# 6_Nand_Flash_NOR_Flash.net
KiCad netlist of a schematic drawn in Altium Designer
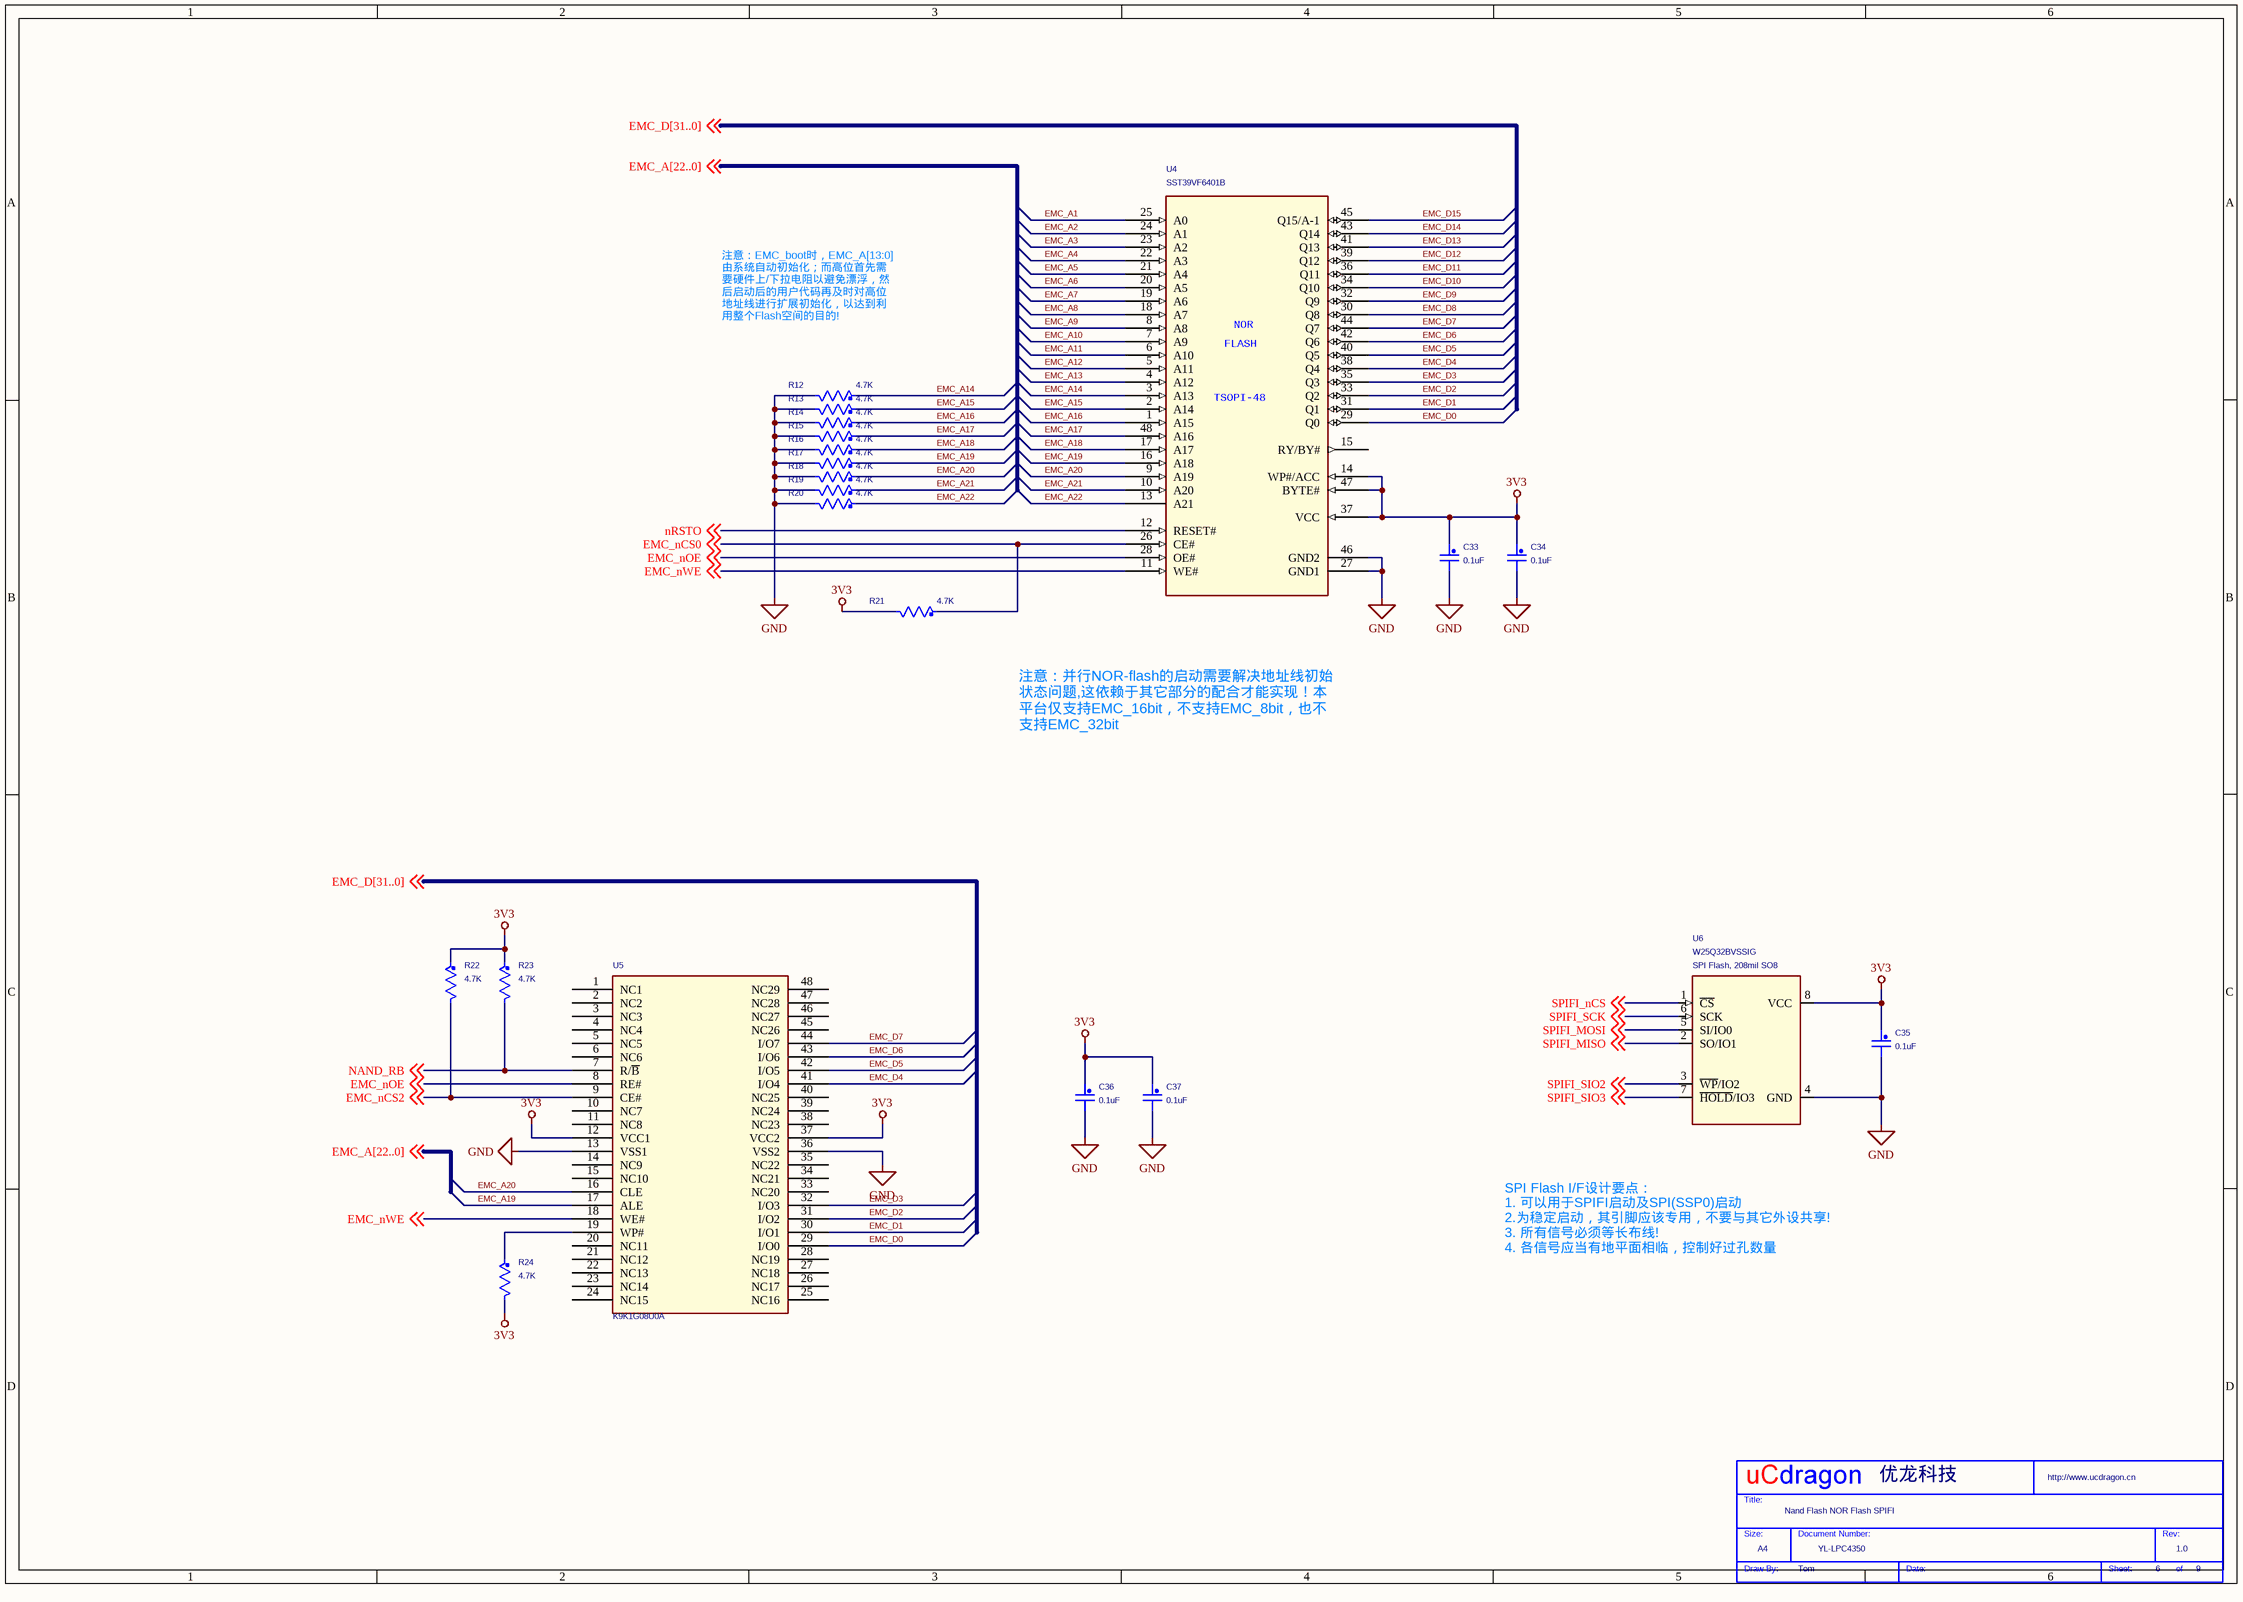
[diagram p0: 6) Nand Flash,NOR Flash.SchDoc]

(export (version "E")
  (design (tool "Eeschema 10.0.6"))
  (components
    (comp (ref "C33")
      (value "0.1uF")
      (footprint "CAP0805")
      (fields (field (name "VOLTAGE") "16V"))
      (libsource (lib "*") (part "C_Generic"))
    )
    (comp (ref "C34")
      (value "0.1uF")
      (footprint "CAP0805")
      (fields (field (name "VOLTAGE") "16V"))
      (libsource (lib "*") (part "C_Generic"))
    )
    (comp (ref "C35")
      (value "0.1uF")
      (footprint "CAP0805")
      (fields (field (name "VOLTAGE") "16V"))
      (libsource (lib "*") (part "C_Generic"))
    )
    (comp (ref "C36")
      (value "0.1uF")
      (footprint "CAP0805")
      (fields (field (name "VOLTAGE") "16V"))
      (libsource (lib "*") (part "C_Generic"))
    )
    (comp (ref "C37")
      (value "0.1uF")
      (footprint "CAP0805")
      (fields (field (name "VOLTAGE") "16V"))
      (libsource (lib "*") (part "C_Generic"))
    )
    (comp (ref "R12") (value "4.7K") (libsource (lib "*") (part "R_Generic_Dup1")))
    (comp (ref "R13") (value "4.7K") (libsource (lib "*") (part "R_Generic_Dup1")))
    (comp (ref "R14") (value "4.7K") (libsource (lib "*") (part "R_Generic_Dup1")))
    (comp (ref "R15") (value "4.7K") (libsource (lib "*") (part "R_Generic_Dup1")))
    (comp (ref "R16") (value "4.7K") (libsource (lib "*") (part "R_Generic_Dup1")))
    (comp (ref "R17") (value "4.7K") (libsource (lib "*") (part "R_Generic_Dup1")))
    (comp (ref "R18") (value "4.7K") (libsource (lib "*") (part "R_Generic_Dup1")))
    (comp (ref "R19") (value "4.7K") (libsource (lib "*") (part "R_Generic_Dup1")))
    (comp (ref "R20") (value "4.7K") (libsource (lib "*") (part "R_Generic_Dup1")))
    (comp (ref "R21") (value "4.7K") (libsource (lib "*") (part "R_Generic_Dup1")))
    (comp (ref "R22") (value "4.7K") (libsource (lib "*") (part "R_Generic_Dup1")))
    (comp (ref "R23") (value "4.7K") (libsource (lib "*") (part "R_Generic_Dup1")))
    (comp (ref "R24") (value "4.7K") (libsource (lib "*") (part "R_Generic_Dup1")))
    (comp (ref "U4")
      (value "SST39VF6401B")
      (footprint "TSOPI-48")
      (libsource (lib "*") (part "MX29LV640EBTI-70G"))
    )
    (comp (ref "U5") (value "K9K1G08U0A") (footprint "TSOP1") (libsource (lib "*") (part "K9K1G08U0A")))
    (comp (ref "U6")
      (value "W25Q32BVSSIG")
      (fields (field (name "NOTE") "SPI Flash, 208mil SO8"))
      (libsource (lib "*") (part "SPI FLASH 4IO WSO8"))
    )
  )
  (nets
    (net (code "1") (name "3V3") (class "Default")
      (node (ref "C33") (pin "1") (pinfunction "1_1") (pintype "passive"))
      (node (ref "C34") (pin "1") (pinfunction "1_1") (pintype "passive"))
      (node (ref "C35") (pin "1") (pinfunction "1_1") (pintype "passive"))
      (node (ref "C36") (pin "1") (pinfunction "1_1") (pintype "passive"))
      (node (ref "C37") (pin "1") (pinfunction "1_1") (pintype "passive"))
      (node (ref "R21") (pin "2") (pinfunction "2_2") (pintype "passive"))
      (node (ref "R22") (pin "1") (pinfunction "1_1") (pintype "passive"))
      (node (ref "R23") (pin "1") (pinfunction "1_1") (pintype "passive"))
      (node (ref "R24") (pin "2") (pinfunction "2_2") (pintype "passive"))
      (node (ref "U4") (pin "14") (pinfunction "WP#/ACC_14") (pintype "input"))
      (node (ref "U4") (pin "37") (pinfunction "VCC_37") (pintype "input"))
      (node (ref "U4") (pin "47") (pinfunction "BYTE#_47") (pintype "input"))
      (node (ref "U5") (pin "12") (pinfunction "VCC1_12") (pintype "passive"))
      (node (ref "U5") (pin "37") (pinfunction "VCC2_37") (pintype "passive"))
      (node (ref "U6") (pin "8") (pinfunction "VCC_8") (pintype "passive"))
    )
    (net (code "2") (name "EMC_A1") (class "Default")
      (node (ref "U4") (pin "25") (pinfunction "A0_25") (pintype "input"))
    )
    (net (code "3") (name "EMC_A2") (class "Default")
      (node (ref "U4") (pin "24") (pinfunction "A1_24") (pintype "input"))
    )
    (net (code "4") (name "EMC_A3") (class "Default")
      (node (ref "U4") (pin "23") (pinfunction "A2_23") (pintype "input"))
    )
    (net (code "5") (name "EMC_A4") (class "Default")
      (node (ref "U4") (pin "22") (pinfunction "A3_22") (pintype "input"))
    )
    (net (code "6") (name "EMC_A5") (class "Default")
      (node (ref "U4") (pin "21") (pinfunction "A4_21") (pintype "input"))
    )
    (net (code "7") (name "EMC_A6") (class "Default")
      (node (ref "U4") (pin "20") (pinfunction "A5_20") (pintype "input"))
    )
    (net (code "8") (name "EMC_A7") (class "Default")
      (node (ref "U4") (pin "19") (pinfunction "A6_19") (pintype "input"))
    )
    (net (code "9") (name "EMC_A8") (class "Default")
      (node (ref "U4") (pin "18") (pinfunction "A7_18") (pintype "input"))
    )
    (net (code "10") (name "EMC_A9") (class "Default")
      (node (ref "U4") (pin "8") (pinfunction "A8_8") (pintype "input"))
    )
    (net (code "11") (name "EMC_A10") (class "Default")
      (node (ref "U4") (pin "7") (pinfunction "A9_7") (pintype "input"))
    )
    (net (code "12") (name "EMC_A11") (class "Default")
      (node (ref "U4") (pin "6") (pinfunction "A10_6") (pintype "input"))
    )
    (net (code "13") (name "EMC_A12") (class "Default")
      (node (ref "U4") (pin "5") (pinfunction "A11_5") (pintype "input"))
    )
    (net (code "14") (name "EMC_A13") (class "Default")
      (node (ref "U4") (pin "4") (pinfunction "A12_4") (pintype "input"))
    )
    (net (code "15") (name "EMC_A14") (class "Default")
      (node (ref "R12") (pin "1") (pinfunction "1_1") (pintype "passive"))
      (node (ref "U4") (pin "3") (pinfunction "A13_3") (pintype "input"))
    )
    (net (code "16") (name "EMC_A15") (class "Default")
      (node (ref "R13") (pin "1") (pinfunction "1_1") (pintype "passive"))
      (node (ref "U4") (pin "2") (pinfunction "A14_2") (pintype "input"))
    )
    (net (code "17") (name "EMC_A16") (class "Default")
      (node (ref "R14") (pin "1") (pinfunction "1_1") (pintype "passive"))
      (node (ref "U4") (pin "1") (pinfunction "A15_1") (pintype "input"))
    )
    (net (code "18") (name "EMC_A17") (class "Default")
      (node (ref "R15") (pin "1") (pinfunction "1_1") (pintype "passive"))
      (node (ref "U4") (pin "48") (pinfunction "A16_48") (pintype "input"))
    )
    (net (code "19") (name "EMC_A18") (class "Default")
      (node (ref "R16") (pin "1") (pinfunction "1_1") (pintype "passive"))
      (node (ref "U4") (pin "17") (pinfunction "A17_17") (pintype "input"))
    )
    (net (code "20") (name "EMC_A19") (class "Default")
      (node (ref "R17") (pin "1") (pinfunction "1_1") (pintype "passive"))
      (node (ref "U4") (pin "16") (pinfunction "A18_16") (pintype "input"))
      (node (ref "U5") (pin "17") (pinfunction "ALE_17") (pintype "passive"))
    )
    (net (code "21") (name "EMC_A20") (class "Default")
      (node (ref "R18") (pin "1") (pinfunction "1_1") (pintype "passive"))
      (node (ref "U4") (pin "9") (pinfunction "A19_9") (pintype "input"))
      (node (ref "U5") (pin "16") (pinfunction "CLE_16") (pintype "passive"))
    )
    (net (code "22") (name "EMC_A21") (class "Default")
      (node (ref "R19") (pin "1") (pinfunction "1_1") (pintype "passive"))
      (node (ref "U4") (pin "10") (pinfunction "A20_10") (pintype "input"))
    )
    (net (code "23") (name "EMC_A22") (class "Default")
      (node (ref "R20") (pin "1") (pinfunction "1_1") (pintype "passive"))
      (node (ref "U4") (pin "13") (pinfunction "A21_13") (pintype "passive"))
    )
    (net (code "25") (name "EMC_D0") (class "Default")
      (node (ref "U4") (pin "29") (pinfunction "Q0_29") (pintype "bidirectional"))
      (node (ref "U5") (pin "29") (pinfunction "I/O0_29") (pintype "passive"))
    )
    (net (code "26") (name "EMC_D1") (class "Default")
      (node (ref "U4") (pin "31") (pinfunction "Q1_31") (pintype "bidirectional"))
      (node (ref "U5") (pin "30") (pinfunction "I/O1_30") (pintype "passive"))
    )
    (net (code "27") (name "EMC_D2") (class "Default")
      (node (ref "U4") (pin "33") (pinfunction "Q2_33") (pintype "bidirectional"))
      (node (ref "U5") (pin "31") (pinfunction "I/O2_31") (pintype "passive"))
    )
    (net (code "28") (name "EMC_D3") (class "Default")
      (node (ref "U4") (pin "35") (pinfunction "Q3_35") (pintype "bidirectional"))
      (node (ref "U5") (pin "32") (pinfunction "I/O3_32") (pintype "passive"))
    )
    (net (code "29") (name "EMC_D4") (class "Default")
      (node (ref "U4") (pin "38") (pinfunction "Q4_38") (pintype "bidirectional"))
      (node (ref "U5") (pin "41") (pinfunction "I/O4_41") (pintype "passive"))
    )
    (net (code "30") (name "EMC_D5") (class "Default")
      (node (ref "U4") (pin "40") (pinfunction "Q5_40") (pintype "bidirectional"))
      (node (ref "U5") (pin "42") (pinfunction "I/O5_42") (pintype "passive"))
    )
    (net (code "31") (name "EMC_D6") (class "Default")
      (node (ref "U4") (pin "42") (pinfunction "Q6_42") (pintype "bidirectional"))
      (node (ref "U5") (pin "43") (pinfunction "I/O6_43") (pintype "passive"))
    )
    (net (code "32") (name "EMC_D7") (class "Default")
      (node (ref "U4") (pin "44") (pinfunction "Q7_44") (pintype "bidirectional"))
      (node (ref "U5") (pin "44") (pinfunction "I/O7_44") (pintype "passive"))
    )
    (net (code "33") (name "EMC_D8") (class "Default")
      (node (ref "U4") (pin "30") (pinfunction "Q8_30") (pintype "bidirectional"))
    )
    (net (code "34") (name "EMC_D9") (class "Default")
      (node (ref "U4") (pin "32") (pinfunction "Q9_32") (pintype "bidirectional"))
    )
    (net (code "35") (name "EMC_D10") (class "Default")
      (node (ref "U4") (pin "34") (pinfunction "Q10_34") (pintype "bidirectional"))
    )
    (net (code "36") (name "EMC_D11") (class "Default")
      (node (ref "U4") (pin "36") (pinfunction "Q11_36") (pintype "bidirectional"))
    )
    (net (code "37") (name "EMC_D12") (class "Default")
      (node (ref "U4") (pin "39") (pinfunction "Q12_39") (pintype "bidirectional"))
    )
    (net (code "38") (name "EMC_D13") (class "Default")
      (node (ref "U4") (pin "41") (pinfunction "Q13_41") (pintype "bidirectional"))
    )
    (net (code "39") (name "EMC_D14") (class "Default")
      (node (ref "U4") (pin "43") (pinfunction "Q14_43") (pintype "bidirectional"))
    )
    (net (code "40") (name "EMC_D15") (class "Default")
      (node (ref "U4") (pin "45") (pinfunction "Q15/A-1_45") (pintype "bidirectional"))
    )
    (net (code "42") (name "EMC_nCS0") (class "Default")
      (node (ref "R21") (pin "1") (pinfunction "1_1") (pintype "passive"))
      (node (ref "U4") (pin "26") (pinfunction "CE#_26") (pintype "input"))
    )
    (net (code "43") (name "EMC_nCS2") (class "Default")
      (node (ref "R22") (pin "2") (pinfunction "2_2") (pintype "passive"))
      (node (ref "U5") (pin "9") (pinfunction "CE#_9") (pintype "passive"))
    )
    (net (code "44") (name "EMC_nOE") (class "Default")
      (node (ref "U4") (pin "28") (pinfunction "OE#_28") (pintype "input"))
      (node (ref "U5") (pin "8") (pinfunction "RE#_8") (pintype "passive"))
    )
    (net (code "45") (name "EMC_nWE") (class "Default")
      (node (ref "U4") (pin "11") (pinfunction "WE#_11") (pintype "input"))
      (node (ref "U5") (pin "18") (pinfunction "WE#_18") (pintype "passive"))
    )
    (net (code "46") (name "GND") (class "Default")
      (node (ref "C33") (pin "2") (pinfunction "2_2") (pintype "passive"))
      (node (ref "C34") (pin "2") (pinfunction "2_2") (pintype "passive"))
      (node (ref "C35") (pin "2") (pinfunction "2_2") (pintype "passive"))
      (node (ref "C36") (pin "2") (pinfunction "2_2") (pintype "passive"))
      (node (ref "C37") (pin "2") (pinfunction "2_2") (pintype "passive"))
      (node (ref "R12") (pin "2") (pinfunction "2_2") (pintype "passive"))
      (node (ref "R13") (pin "2") (pinfunction "2_2") (pintype "passive"))
      (node (ref "R14") (pin "2") (pinfunction "2_2") (pintype "passive"))
      (node (ref "R15") (pin "2") (pinfunction "2_2") (pintype "passive"))
      (node (ref "R16") (pin "2") (pinfunction "2_2") (pintype "passive"))
      (node (ref "R17") (pin "2") (pinfunction "2_2") (pintype "passive"))
      (node (ref "R18") (pin "2") (pinfunction "2_2") (pintype "passive"))
      (node (ref "R19") (pin "2") (pinfunction "2_2") (pintype "passive"))
      (node (ref "R20") (pin "2") (pinfunction "2_2") (pintype "passive"))
      (node (ref "U4") (pin "27") (pinfunction "GND1_27") (pintype "passive"))
      (node (ref "U4") (pin "46") (pinfunction "GND2_46") (pintype "passive"))
      (node (ref "U5") (pin "13") (pinfunction "VSS1_13") (pintype "passive"))
      (node (ref "U5") (pin "36") (pinfunction "VSS2_36") (pintype "passive"))
      (node (ref "U6") (pin "4") (pinfunction "GND_4") (pintype "passive"))
    )
    (net (code "47") (name "NAND_RB") (class "Default")
      (node (ref "R23") (pin "2") (pinfunction "2_2") (pintype "passive"))
      (node (ref "U5") (pin "7") (pinfunction "R/~{B}_7") (pintype "passive"))
    )
    (net (code "48") (name "Net-(U5-WP#)") (class "Default")
      (node (ref "R24") (pin "1") (pinfunction "1_1") (pintype "passive"))
      (node (ref "U5") (pin "19") (pinfunction "WP#_19") (pintype "passive"))
    )
    (net (code "49") (name "SPIFI_MISO") (class "Default")
      (node (ref "U6") (pin "2") (pinfunction "SO/IO1_2") (pintype "passive"))
    )
    (net (code "50") (name "SPIFI_MOSI") (class "Default")
      (node (ref "U6") (pin "5") (pinfunction "SI/IO0_5") (pintype "passive"))
    )
    (net (code "51") (name "SPIFI_SCK") (class "Default")
      (node (ref "U6") (pin "6") (pinfunction "SCK_6") (pintype "input"))
    )
    (net (code "52") (name "SPIFI_SIO2") (class "Default")
      (node (ref "U6") (pin "3") (pinfunction "~{WP}/IO2_3") (pintype "passive"))
    )
    (net (code "53") (name "SPIFI_SIO3") (class "Default")
      (node (ref "U6") (pin "7") (pinfunction "~{HOLD}/IO3_7") (pintype "passive"))
    )
    (net (code "54") (name "SPIFI_nCS") (class "Default")
      (node (ref "U6") (pin "1") (pinfunction "~{CS}_1") (pintype "input"))
    )
    (net (code "55") (name "nRSTO") (class "Default")
      (node (ref "U4") (pin "12") (pinfunction "RESET#_12") (pintype "input"))
    )
    (net (code "56") (name "unconnected-(U4-RY{slash}BY#-Pad15)") (class "Default")
      (node (ref "U4") (pin "15") (pinfunction "RY/BY#_15") (pintype "output"))
    )
    (net (code "57") (name "unconnected-(U5-NC1-Pad1)") (class "Default")
      (node (ref "U5") (pin "1") (pinfunction "NC1_1") (pintype "passive"))
    )
    (net (code "58") (name "unconnected-(U5-NC2-Pad2)") (class "Default")
      (node (ref "U5") (pin "2") (pinfunction "NC2_2") (pintype "passive"))
    )
    (net (code "59") (name "unconnected-(U5-NC3-Pad3)") (class "Default")
      (node (ref "U5") (pin "3") (pinfunction "NC3_3") (pintype "passive"))
    )
    (net (code "60") (name "unconnected-(U5-NC4-Pad4)") (class "Default")
      (node (ref "U5") (pin "4") (pinfunction "NC4_4") (pintype "passive"))
    )
    (net (code "61") (name "unconnected-(U5-NC5-Pad5)") (class "Default")
      (node (ref "U5") (pin "5") (pinfunction "NC5_5") (pintype "passive"))
    )
    (net (code "62") (name "unconnected-(U5-NC6-Pad6)") (class "Default")
      (node (ref "U5") (pin "6") (pinfunction "NC6_6") (pintype "passive"))
    )
    (net (code "63") (name "unconnected-(U5-NC7-Pad10)") (class "Default")
      (node (ref "U5") (pin "10") (pinfunction "NC7_10") (pintype "passive"))
    )
    (net (code "64") (name "unconnected-(U5-NC8-Pad11)") (class "Default")
      (node (ref "U5") (pin "11") (pinfunction "NC8_11") (pintype "passive"))
    )
    (net (code "65") (name "unconnected-(U5-NC9-Pad14)") (class "Default")
      (node (ref "U5") (pin "14") (pinfunction "NC9_14") (pintype "passive"))
    )
    (net (code "66") (name "unconnected-(U5-NC10-Pad15)") (class "Default")
      (node (ref "U5") (pin "15") (pinfunction "NC10_15") (pintype "passive"))
    )
    (net (code "67") (name "unconnected-(U5-NC11-Pad20)") (class "Default")
      (node (ref "U5") (pin "20") (pinfunction "NC11_20") (pintype "passive"))
    )
    (net (code "68") (name "unconnected-(U5-NC12-Pad21)") (class "Default")
      (node (ref "U5") (pin "21") (pinfunction "NC12_21") (pintype "passive"))
    )
    (net (code "69") (name "unconnected-(U5-NC13-Pad22)") (class "Default")
      (node (ref "U5") (pin "22") (pinfunction "NC13_22") (pintype "passive"))
    )
    (net (code "70") (name "unconnected-(U5-NC14-Pad23)") (class "Default")
      (node (ref "U5") (pin "23") (pinfunction "NC14_23") (pintype "passive"))
    )
    (net (code "71") (name "unconnected-(U5-NC15-Pad24)") (class "Default")
      (node (ref "U5") (pin "24") (pinfunction "NC15_24") (pintype "passive"))
    )
    (net (code "72") (name "unconnected-(U5-NC16-Pad25)") (class "Default")
      (node (ref "U5") (pin "25") (pinfunction "NC16_25") (pintype "passive"))
    )
    (net (code "73") (name "unconnected-(U5-NC17-Pad26)") (class "Default")
      (node (ref "U5") (pin "26") (pinfunction "NC17_26") (pintype "passive"))
    )
    (net (code "74") (name "unconnected-(U5-NC18-Pad27)") (class "Default")
      (node (ref "U5") (pin "27") (pinfunction "NC18_27") (pintype "passive"))
    )
    (net (code "75") (name "unconnected-(U5-NC19-Pad28)") (class "Default")
      (node (ref "U5") (pin "28") (pinfunction "NC19_28") (pintype "passive"))
    )
    (net (code "76") (name "unconnected-(U5-NC20-Pad33)") (class "Default")
      (node (ref "U5") (pin "33") (pinfunction "NC20_33") (pintype "passive"))
    )
    (net (code "77") (name "unconnected-(U5-NC21-Pad34)") (class "Default")
      (node (ref "U5") (pin "34") (pinfunction "NC21_34") (pintype "passive"))
    )
    (net (code "78") (name "unconnected-(U5-NC22-Pad35)") (class "Default")
      (node (ref "U5") (pin "35") (pinfunction "NC22_35") (pintype "passive"))
    )
    (net (code "79") (name "unconnected-(U5-NC23-Pad38)") (class "Default")
      (node (ref "U5") (pin "38") (pinfunction "NC23_38") (pintype "passive"))
    )
    (net (code "80") (name "unconnected-(U5-NC24-Pad39)") (class "Default")
      (node (ref "U5") (pin "39") (pinfunction "NC24_39") (pintype "passive"))
    )
    (net (code "81") (name "unconnected-(U5-NC25-Pad40)") (class "Default")
      (node (ref "U5") (pin "40") (pinfunction "NC25_40") (pintype "passive"))
    )
    (net (code "82") (name "unconnected-(U5-NC26-Pad45)") (class "Default")
      (node (ref "U5") (pin "45") (pinfunction "NC26_45") (pintype "passive"))
    )
    (net (code "83") (name "unconnected-(U5-NC27-Pad46)") (class "Default")
      (node (ref "U5") (pin "46") (pinfunction "NC27_46") (pintype "passive"))
    )
    (net (code "84") (name "unconnected-(U5-NC28-Pad47)") (class "Default")
      (node (ref "U5") (pin "47") (pinfunction "NC28_47") (pintype "passive"))
    )
    (net (code "85") (name "unconnected-(U5-NC29-Pad48)") (class "Default")
      (node (ref "U5") (pin "48") (pinfunction "NC29_48") (pintype "passive"))
    )
  )
)
